# TEMP_TMP007_I2C_V2.net
KiCad netlist of a schematic drawn in EAGLE
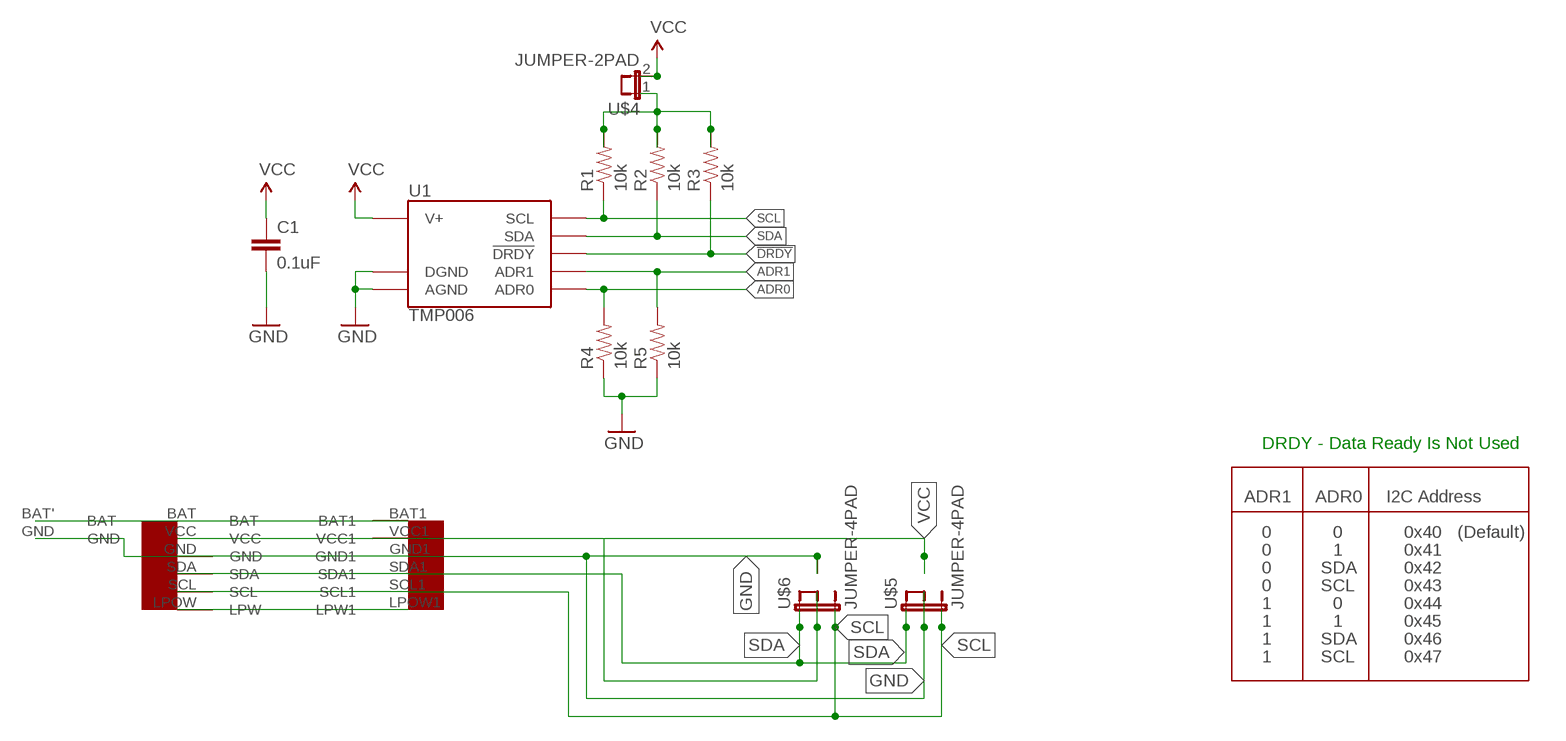
[diagram p0: schematic, sheet 1]

(export (version "E")
  (design (tool "Eeschema 10.0.6"))
  (components
    (comp (ref "C1")
      (value "0.1uF")
      (footprint "eagle-import:0603-CAP")
      (libsource (lib "eagle-import") (part "CAP0603-CAP"))
    )
    (comp (ref "R1")
      (value "10k")
      (footprint "eagle-import:0603-RES")
      (libsource (lib "eagle-import") (part "RESISTOR0603-RES"))
    )
    (comp (ref "R2")
      (value "10k")
      (footprint "eagle-import:0603-RES")
      (libsource (lib "eagle-import") (part "RESISTOR0603-RES"))
    )
    (comp (ref "R3")
      (value "10k")
      (footprint "eagle-import:0603-RES")
      (libsource (lib "eagle-import") (part "RESISTOR0603-RES"))
    )
    (comp (ref "R4")
      (value "10k")
      (footprint "eagle-import:0603-RES")
      (libsource (lib "eagle-import") (part "RESISTOR0603-RES"))
    )
    (comp (ref "R5")
      (value "10k")
      (footprint "eagle-import:0603-RES")
      (libsource (lib "eagle-import") (part "RESISTOR0603-RES"))
    )
    (comp (ref "U$1")
      (value "EZ-I2CHEADERV1")
      (footprint "eagle-import:EZ-I2CHEADERV1")
      (libsource (lib "eagle-import") (part "EZ-I2CHEADERV1"))
    )
    (comp (ref "U$3")
      (value "MINI_BATTERY_HOLES")
      (footprint "eagle-import:MINI_BATTERY_HOLES")
      (libsource (lib "eagle-import") (part "MINI_BATTERY_HOLES"))
    )
    (comp (ref "U$4")
      (value "JUMPER-2PAD")
      (footprint "eagle-import:JUMPER-2PAD")
      (libsource (lib "eagle-import") (part "JUMPER-2PAD"))
    )
    (comp (ref "U$5")
      (value "JUMPER-4PAD")
      (footprint "eagle-import:JUMPER-4PAD")
      (libsource (lib "eagle-import") (part "JUMPER-4PAD"))
    )
    (comp (ref "U$6")
      (value "JUMPER-4PAD")
      (footprint "eagle-import:JUMPER-4PAD")
      (libsource (lib "eagle-import") (part "JUMPER-4PAD"))
    )
    (comp (ref "U1")
      (value "TMP006")
      (footprint "eagle-import:BGA8DS")
      (libsource (lib "eagle-import") (part "TMP006"))
    )
  )
  (nets
    (net (code "1") (name "/~{DRDY}") (class "Default")
      (node (ref "R3") (pin "1") (pinfunction "1_1") (pintype "passive"))
      (node (ref "U1") (pin "C2") (pinfunction "~{DRDY}_C2") (pintype "bidirectional"))
    )
    (net (code "2") (name "ADR0") (class "Default")
      (node (ref "R4") (pin "2") (pinfunction "2_2") (pintype "passive"))
      (node (ref "U1") (pin "C1") (pinfunction "ADR0_C1") (pintype "bidirectional"))
    )
    (net (code "3") (name "ADR1") (class "Default")
      (node (ref "R5") (pin "2") (pinfunction "2_2") (pintype "passive"))
      (node (ref "U1") (pin "B1") (pinfunction "ADR1_B1") (pintype "bidirectional"))
    )
    (net (code "4") (name "GND") (class "Default")
      (node (ref "C1") (pin "2") (pinfunction "2_2") (pintype "passive"))
      (node (ref "R4") (pin "1") (pinfunction "1_1") (pintype "passive"))
      (node (ref "R5") (pin "1") (pinfunction "1_1") (pintype "passive"))
      (node (ref "U$1") (pin "GND") (pinfunction "GND_GND") (pintype "bidirectional"))
      (node (ref "U$1") (pin "GND1") (pinfunction "GND1_GND1") (pintype "bidirectional"))
      (node (ref "U$3") (pin "GND") (pinfunction "GND_GND") (pintype "bidirectional"))
      (node (ref "U$5") (pin "2") (pinfunction "2_2") (pintype "passive"))
      (node (ref "U$6") (pin "4") (pinfunction "4_4") (pintype "passive"))
      (node (ref "U1") (pin "A1") (pinfunction "DGND_A1") (pintype "bidirectional"))
      (node (ref "U1") (pin "A2") (pinfunction "AGND_A2") (pintype "bidirectional"))
    )
    (net (code "5") (name "Net-(R1-Pad2)") (class "Default")
      (node (ref "R1") (pin "2") (pinfunction "2_2") (pintype "passive"))
      (node (ref "R2") (pin "2") (pinfunction "2_2") (pintype "passive"))
      (node (ref "R3") (pin "2") (pinfunction "2_2") (pintype "passive"))
      (node (ref "U$4") (pin "1") (pinfunction "1_1") (pintype "passive"))
    )
    (net (code "6") (name "Net-(U$1-LPW)") (class "Default")
      (node (ref "U$1") (pin "LPOW") (pinfunction "LPW_LPOW") (pintype "bidirectional"))
      (node (ref "U$1") (pin "LPOW1") (pinfunction "LPW1_LPOW1") (pintype "bidirectional"))
    )
    (net (code "7") (name "Net-(U$3-BAT)") (class "Default")
      (node (ref "U$1") (pin "BAT") (pinfunction "BAT_BAT") (pintype "bidirectional"))
      (node (ref "U$1") (pin "BAT1") (pinfunction "BAT1_BAT1") (pintype "bidirectional"))
      (node (ref "U$3") (pin "BAT'") (pinfunction "BAT_BAT'") (pintype "bidirectional"))
    )
    (net (code "8") (name "SCL") (class "Default")
      (node (ref "R1") (pin "1") (pinfunction "1_1") (pintype "passive"))
      (node (ref "U$1") (pin "SCL") (pinfunction "SCL_SCL") (pintype "bidirectional"))
      (node (ref "U$1") (pin "SCL1") (pinfunction "SCL1_SCL1") (pintype "bidirectional"))
      (node (ref "U$5") (pin "3") (pinfunction "3_3") (pintype "passive"))
      (node (ref "U$6") (pin "3") (pinfunction "3_3") (pintype "passive"))
      (node (ref "U1") (pin "B3") (pinfunction "SCL_B3") (pintype "bidirectional"))
    )
    (net (code "9") (name "SDA") (class "Default")
      (node (ref "R2") (pin "1") (pinfunction "1_1") (pintype "passive"))
      (node (ref "U$1") (pin "SDA") (pinfunction "SDA_SDA") (pintype "bidirectional"))
      (node (ref "U$1") (pin "SDA1") (pinfunction "SDA1_SDA1") (pintype "bidirectional"))
      (node (ref "U$5") (pin "1") (pinfunction "1_1") (pintype "passive"))
      (node (ref "U$6") (pin "1") (pinfunction "1_1") (pintype "passive"))
      (node (ref "U1") (pin "C3") (pinfunction "SDA_C3") (pintype "bidirectional"))
    )
    (net (code "10") (name "VCC") (class "Default")
      (node (ref "C1") (pin "1") (pinfunction "1_1") (pintype "passive"))
      (node (ref "U$1") (pin "VCC") (pinfunction "VCC_VCC") (pintype "bidirectional"))
      (node (ref "U$1") (pin "VCC1") (pinfunction "VCC1_VCC1") (pintype "bidirectional"))
      (node (ref "U$4") (pin "2") (pinfunction "2_2") (pintype "passive"))
      (node (ref "U$5") (pin "4") (pinfunction "4_4") (pintype "passive"))
      (node (ref "U$6") (pin "2") (pinfunction "2_2") (pintype "passive"))
      (node (ref "U1") (pin "A3") (pinfunction "V+_A3") (pintype "bidirectional"))
    )
  )
)
